# IR_Remote_LEDs.net
KiCad netlist of a schematic drawn in Altium Designer
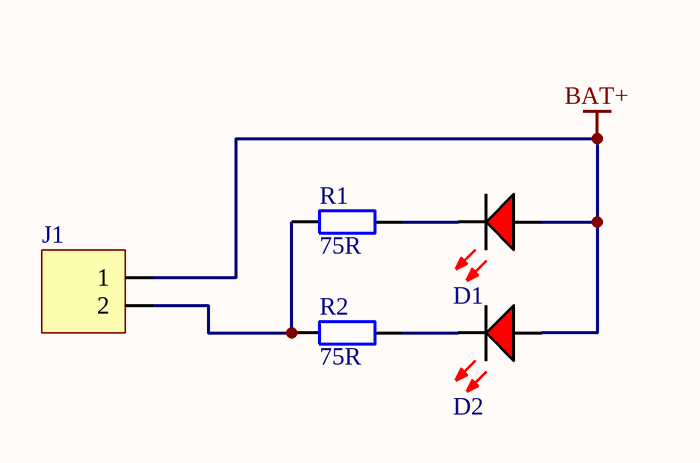
[diagram p0: IR_Remote_LEDs.SchDoc]

(export (version "E")
  (design (tool "Eeschema 10.0.6"))
  (components
    (comp (ref "D1")
      (value "LED Red")
      (footprint "LED5MM")
      (description "LED 5mm Red")
      (fields (field (name "MANUFACTURER") "Generic Components") (field (name "PUBLISHER") "Altium Limited"))
      (libsource (lib "MyLibrary") (part "LED_5MM_RED"))
    )
    (comp (ref "D2")
      (value "LED Red")
      (footprint "LED5MM")
      (description "LED 5mm Red")
      (fields (field (name "MANUFACTURER") "Generic Components") (field (name "PUBLISHER") "Altium Limited"))
      (libsource (lib "MyLibrary") (part "LED_5MM_RED"))
    )
    (comp (ref "J1")
      (value "Connector - JST PH 2-Pin")
      (footprint "JST-P2B-PH")
      (fields (field (name "PUBLISHER") "Altium Limited"))
      (libsource (lib "MyLibrary") (part "JST-B2B-PH-A"))
    )
    (comp (ref "R1")
      (value "75R")
      (footprint "CR1608-0603_N")
      (description "100mW SMT ±1% 0603 Chip Resistor")
      (fields
        (field (name "MANUFACTURER") "Generic Components")
        (field (name "PUBLISHER") "Altium Hobart Technology Centre")
      )
      (libsource (lib "MyLibrary") (part "Res_CR0603_75R"))
    )
    (comp (ref "R2")
      (value "75R")
      (footprint "CR1608-0603_N")
      (description "100mW SMT ±1% 0603 Chip Resistor")
      (fields
        (field (name "MANUFACTURER") "Generic Components")
        (field (name "PUBLISHER") "Altium Hobart Technology Centre")
      )
      (libsource (lib "MyLibrary") (part "Res_CR0603_75R"))
    )
  )
  (nets
    (net (code "1") (name "BAT+") (class "Default")
      (node (ref "D1") (pin "A") (pinfunction "A_A") (pintype "passive"))
      (node (ref "D2") (pin "A") (pinfunction "A_A") (pintype "passive"))
      (node (ref "J1") (pin "1") (pinfunction "1_1") (pintype "passive"))
    )
    (net (code "2") (name "Net-(D1-PadK)") (class "Default")
      (node (ref "D1") (pin "K") (pinfunction "K_K") (pintype "passive"))
      (node (ref "R1") (pin "2") (pinfunction "2_2") (pintype "passive"))
    )
    (net (code "3") (name "Net-(D2-PadK)") (class "Default")
      (node (ref "D2") (pin "K") (pinfunction "K_K") (pintype "passive"))
      (node (ref "R2") (pin "2") (pinfunction "2_2") (pintype "passive"))
    )
    (net (code "4") (name "Net-(J1-Pad2)") (class "Default")
      (node (ref "J1") (pin "2") (pinfunction "2_2") (pintype "passive"))
      (node (ref "R1") (pin "1") (pinfunction "1_1") (pintype "passive"))
      (node (ref "R2") (pin "1") (pinfunction "1_1") (pintype "passive"))
    )
  )
)
